# PCB_Draft_0.net
KiCad netlist of a schematic drawn in EAGLE
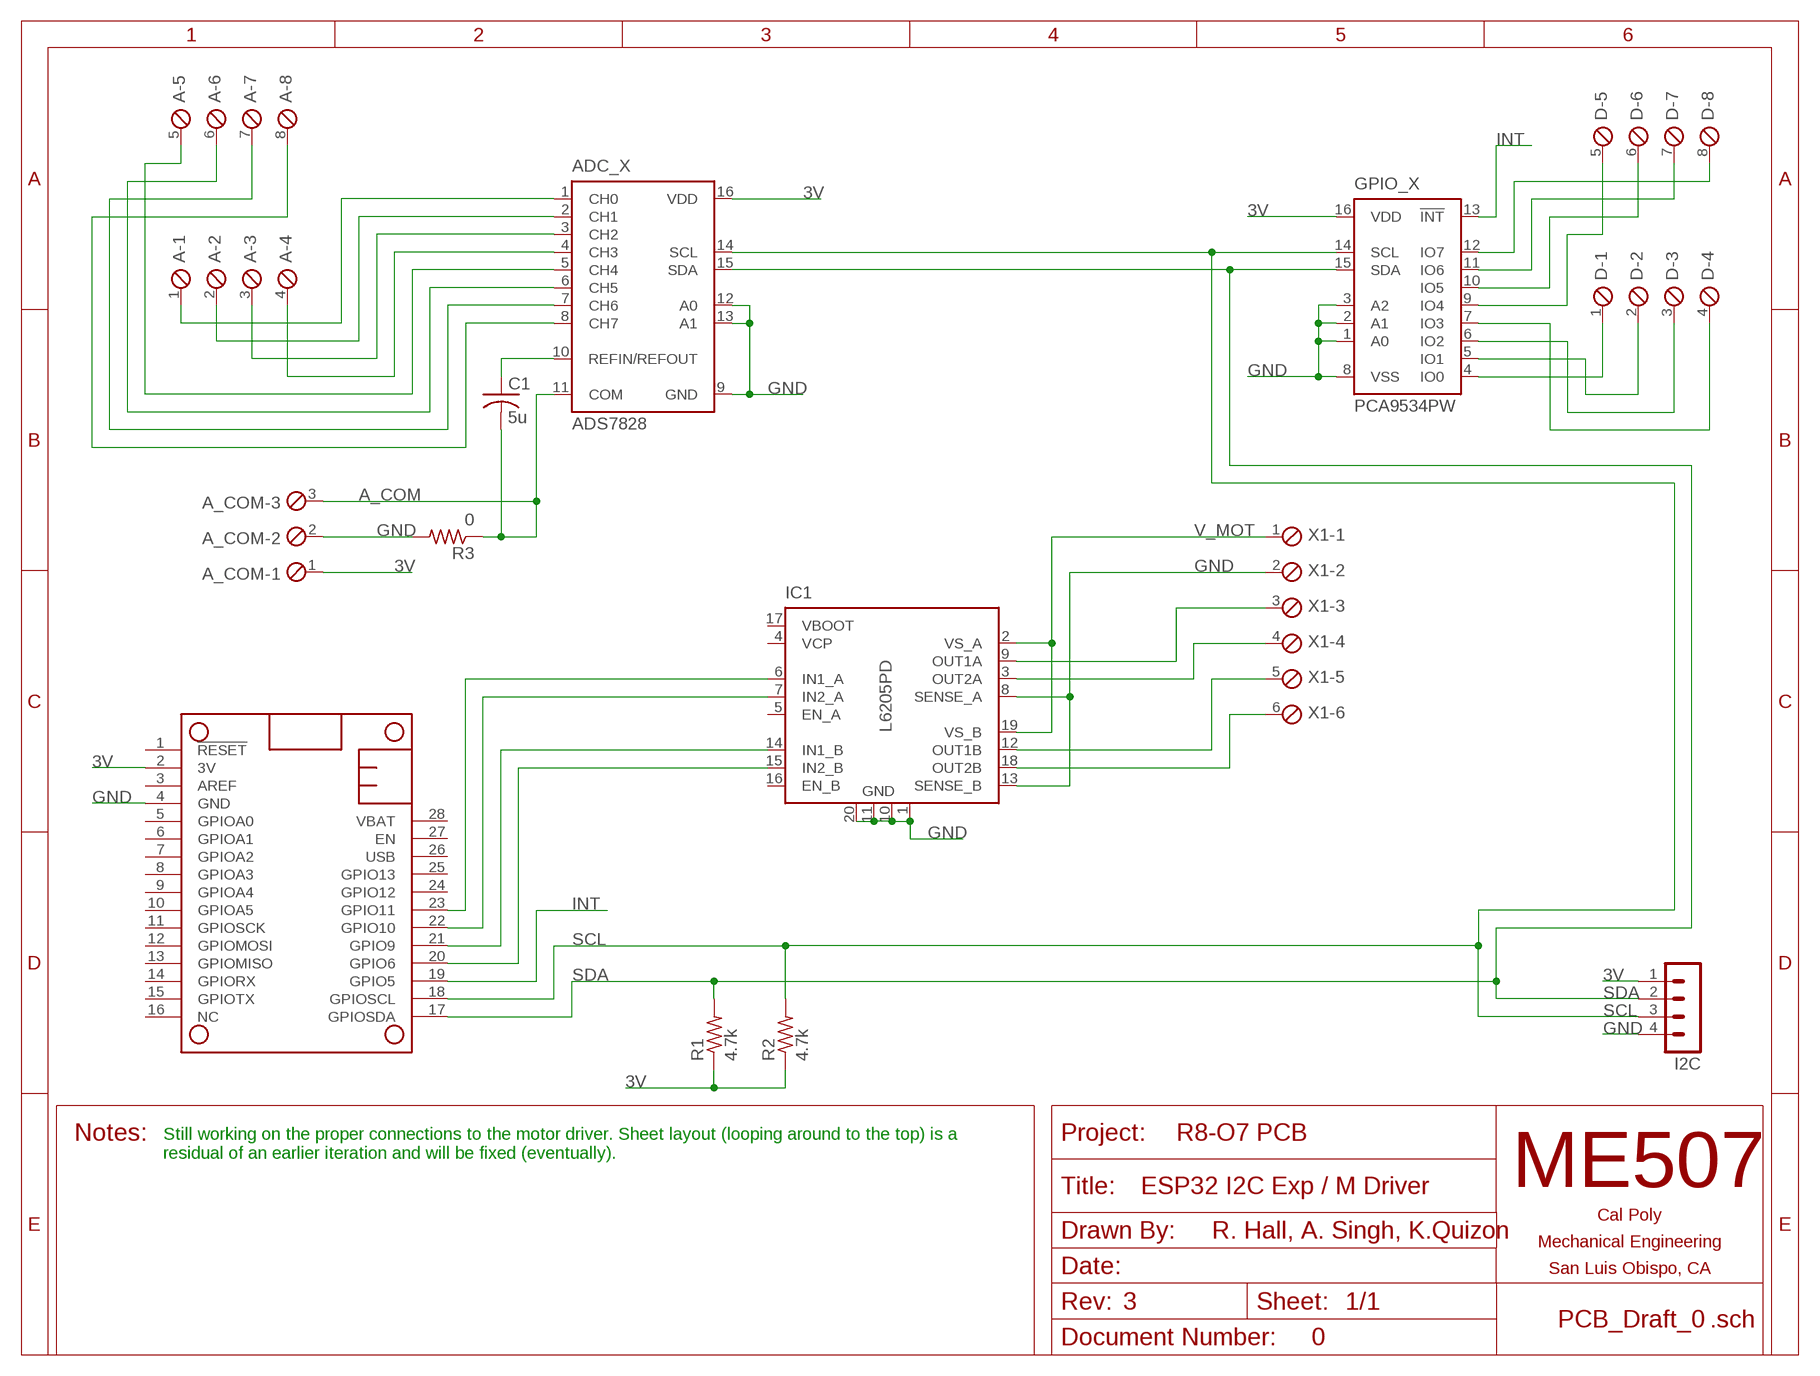
[diagram p0: schematic, sheet 1]

(export (version "E")
  (design (tool "Eeschema 10.0.6"))
  (components
    (comp (ref "A")
      (value "SCREWTERM_8P_254")
      (footprint "eagle-import:8POL254")
      (libsource (lib "eagle-import") (part "SCREWTERM_8P_254"))
    )
    (comp (ref "ADC_X")
      (value "ADS7828")
      (footprint "eagle-import:TSSOP16-PW")
      (fields (field (name "MF") "TEXAS INSTRUMENTS") (field (name "MPN") "ADS7828E/250"))
      (libsource (lib "eagle-import") (part "ADS7828"))
    )
    (comp (ref "A_COM")
      (value "SCREWTERM_3P_254")
      (footprint "eagle-import:3POL254")
      (libsource (lib "eagle-import") (part "SCREWTERM_3P_254"))
    )
    (comp (ref "C1")
      (value "5u")
      (footprint "eagle-import:C0805")
      (libsource (lib "eagle-import") (part "C-USC0805"))
    )
    (comp (ref "D")
      (value "SCREWTERM_8P_254")
      (footprint "eagle-import:8POL254")
      (libsource (lib "eagle-import") (part "SCREWTERM_8P_254"))
    )
    (comp (ref "GPIO_X")
      (value "PCA9534PW")
      (footprint "eagle-import:TSSOP16")
      (libsource (lib "eagle-import") (part "PCA9534PW"))
    )
    (comp (ref "I2C")
      (value "MA04-1")
      (footprint "eagle-import:MA04-1")
      (libsource (lib "eagle-import") (part "MA04-1"))
    )
    (comp (ref "IC1")
      (value "L6205PD")
      (footprint "eagle-import:POWERSO-20")
      (fields (field (name "MF") "Arrow Electronics"))
      (libsource (lib "eagle-import") (part "L6205PD"))
    )
    (comp (ref "MS1")
      (value "FEATHERWINGEXTENDED_BOTH_ENDS")
      (footprint "eagle-import:FEATHERWING")
      (libsource (lib "eagle-import") (part "FEATHERWINGEXTENDED_BOTH_ENDS"))
    )
    (comp (ref "R1")
      (value "4.7k")
      (footprint "eagle-import:R0805")
      (libsource (lib "eagle-import") (part "R-US_R0805"))
    )
    (comp (ref "R2")
      (value "4.7k")
      (footprint "eagle-import:R0805")
      (libsource (lib "eagle-import") (part "R-US_R0805"))
    )
    (comp (ref "R3")
      (value "0")
      (footprint "eagle-import:M0805")
      (libsource (lib "eagle-import") (part "R-US_M0805"))
    )
    (comp (ref "X1")
      (value "SCREWTERM_6P_254")
      (footprint "eagle-import:6POL254")
      (libsource (lib "eagle-import") (part "SCREWTERM_6P_254"))
    )
  )
  (nets
    (net (code "1") (name "/3V") (class "Default")
      (node (ref "ADC_X") (pin "16") (pinfunction "VDD_16") (pintype "power_in"))
      (node (ref "A_COM") (pin "1") (pinfunction "1_1") (pintype "passive"))
      (node (ref "GPIO_X") (pin "16") (pinfunction "VDD_16") (pintype "power_in"))
      (node (ref "I2C") (pin "1") (pinfunction "1_1") (pintype "passive"))
      (node (ref "MS1") (pin "2") (pinfunction "3V_2") (pintype "power_in"))
      (node (ref "R1") (pin "1") (pinfunction "1_1") (pintype "passive"))
      (node (ref "R2") (pin "1") (pinfunction "1_1") (pintype "passive"))
    )
    (net (code "2") (name "/A_COM") (class "Default")
      (node (ref "ADC_X") (pin "11") (pinfunction "COM_11") (pintype "input"))
      (node (ref "A_COM") (pin "3") (pinfunction "1_3") (pintype "passive"))
      (node (ref "C1") (pin "2") (pinfunction "2_2") (pintype "passive"))
      (node (ref "R3") (pin "1") (pinfunction "1_1") (pintype "passive"))
    )
    (net (code "3") (name "/GND") (class "Default")
      (node (ref "ADC_X") (pin "12") (pinfunction "A0_12") (pintype "input"))
      (node (ref "ADC_X") (pin "13") (pinfunction "A1_13") (pintype "input"))
      (node (ref "ADC_X") (pin "9") (pinfunction "GND_9") (pintype "power_in"))
      (node (ref "A_COM") (pin "2") (pinfunction "1_2") (pintype "passive"))
      (node (ref "GPIO_X") (pin "1") (pinfunction "A0_1") (pintype "input"))
      (node (ref "GPIO_X") (pin "2") (pinfunction "A1_2") (pintype "input"))
      (node (ref "GPIO_X") (pin "3") (pinfunction "A2_3") (pintype "input"))
      (node (ref "GPIO_X") (pin "8") (pinfunction "VSS_8") (pintype "power_in"))
      (node (ref "I2C") (pin "4") (pinfunction "4_4") (pintype "passive"))
      (node (ref "IC1") (pin "1") (pinfunction "GND_1") (pintype "power_in"))
      (node (ref "IC1") (pin "10") (pinfunction "GND_10") (pintype "power_in"))
      (node (ref "IC1") (pin "11") (pinfunction "GND_11") (pintype "power_in"))
      (node (ref "IC1") (pin "13") (pinfunction "SENSE_B_13") (pintype "input"))
      (node (ref "IC1") (pin "20") (pinfunction "GND_20") (pintype "power_in"))
      (node (ref "IC1") (pin "8") (pinfunction "SENSE_A_8") (pintype "input"))
      (node (ref "MS1") (pin "4") (pinfunction "GND_4") (pintype "power_in"))
      (node (ref "R3") (pin "2") (pinfunction "2_2") (pintype "passive"))
      (node (ref "X1") (pin "2") (pinfunction "1_2") (pintype "passive"))
    )
    (net (code "4") (name "/INT") (class "Default")
      (node (ref "GPIO_X") (pin "13") (pinfunction "~{INT}_13") (pintype "open_collector"))
      (node (ref "MS1") (pin "19") (pinfunction "GPIO5_19") (pintype "bidirectional"))
    )
    (net (code "5") (name "/SCL") (class "Default")
      (node (ref "ADC_X") (pin "14") (pinfunction "SCL_14") (pintype "input"))
      (node (ref "GPIO_X") (pin "14") (pinfunction "SCL_14") (pintype "input"))
      (node (ref "I2C") (pin "3") (pinfunction "3_3") (pintype "passive"))
      (node (ref "MS1") (pin "18") (pinfunction "GPIOSCL_18") (pintype "bidirectional"))
      (node (ref "R2") (pin "2") (pinfunction "2_2") (pintype "passive"))
    )
    (net (code "6") (name "/SDA") (class "Default")
      (node (ref "ADC_X") (pin "15") (pinfunction "SDA_15") (pintype "bidirectional"))
      (node (ref "GPIO_X") (pin "15") (pinfunction "SDA_15") (pintype "bidirectional"))
      (node (ref "I2C") (pin "2") (pinfunction "2_2") (pintype "passive"))
      (node (ref "MS1") (pin "17") (pinfunction "GPIOSDA_17") (pintype "bidirectional"))
      (node (ref "R1") (pin "2") (pinfunction "2_2") (pintype "passive"))
    )
    (net (code "7") (name "/USB") (class "Default")
      (node (ref "MS1") (pin "26") (pinfunction "USB_26") (pintype "power_in"))
    )
    (net (code "8") (name "/VBAT") (class "Default")
      (node (ref "MS1") (pin "28") (pinfunction "VBAT_28") (pintype "power_in"))
    )
    (net (code "9") (name "/VBOOT") (class "Default")
      (node (ref "IC1") (pin "17") (pinfunction "VBOOT_17") (pintype "power_in"))
    )
    (net (code "10") (name "/VCP") (class "Default")
      (node (ref "IC1") (pin "4") (pinfunction "VCP_4") (pintype "power_in"))
    )
    (net (code "11") (name "/V_MOT") (class "Default")
      (node (ref "IC1") (pin "19") (pinfunction "VS_B_19") (pintype "power_in"))
      (node (ref "IC1") (pin "2") (pinfunction "VS_A_2") (pintype "power_in"))
      (node (ref "X1") (pin "1") (pinfunction "1_1") (pintype "passive"))
    )
    (net (code "12") (name "Net-(AB-1)") (class "Default")
      (node (ref "A") (pin "2") (pinfunction "1_2") (pintype "passive"))
      (node (ref "ADC_X") (pin "2") (pinfunction "CH1_2") (pintype "input"))
    )
    (net (code "13") (name "Net-(AC-1)") (class "Default")
      (node (ref "A") (pin "3") (pinfunction "1_3") (pintype "passive"))
      (node (ref "ADC_X") (pin "3") (pinfunction "CH2_3") (pintype "input"))
    )
    (net (code "14") (name "Net-(AD-1)") (class "Default")
      (node (ref "A") (pin "4") (pinfunction "1_4") (pintype "passive"))
      (node (ref "ADC_X") (pin "4") (pinfunction "CH3_4") (pintype "input"))
    )
    (net (code "15") (name "Net-(ADC_X-CH0)") (class "Default")
      (node (ref "A") (pin "1") (pinfunction "1_1") (pintype "passive"))
      (node (ref "ADC_X") (pin "1") (pinfunction "CH0_1") (pintype "input"))
    )
    (net (code "16") (name "Net-(ADC_X-CH4)") (class "Default")
      (node (ref "A") (pin "5") (pinfunction "1_5") (pintype "passive"))
      (node (ref "ADC_X") (pin "5") (pinfunction "CH4_5") (pintype "input"))
    )
    (net (code "17") (name "Net-(ADC_X-CH5)") (class "Default")
      (node (ref "A") (pin "6") (pinfunction "1_6") (pintype "passive"))
      (node (ref "ADC_X") (pin "6") (pinfunction "CH5_6") (pintype "input"))
    )
    (net (code "18") (name "Net-(ADC_X-CH6)") (class "Default")
      (node (ref "A") (pin "7") (pinfunction "1_7") (pintype "passive"))
      (node (ref "ADC_X") (pin "7") (pinfunction "CH6_7") (pintype "input"))
    )
    (net (code "19") (name "Net-(ADC_X-CH7)") (class "Default")
      (node (ref "A") (pin "8") (pinfunction "1_8") (pintype "passive"))
      (node (ref "ADC_X") (pin "8") (pinfunction "CH7_8") (pintype "input"))
    )
    (net (code "20") (name "Net-(ADC_X-REFIN{slash}REFOUT)") (class "Default")
      (node (ref "ADC_X") (pin "10") (pinfunction "REFIN/REFOUT_10") (pintype "passive"))
      (node (ref "C1") (pin "1") (pinfunction "1_1") (pintype "passive"))
    )
    (net (code "21") (name "Net-(DB-1)") (class "Default")
      (node (ref "D") (pin "2") (pinfunction "1_2") (pintype "passive"))
      (node (ref "GPIO_X") (pin "5") (pinfunction "IO1_5") (pintype "bidirectional"))
    )
    (net (code "22") (name "Net-(DC-1)") (class "Default")
      (node (ref "D") (pin "3") (pinfunction "1_3") (pintype "passive"))
      (node (ref "GPIO_X") (pin "6") (pinfunction "IO2_6") (pintype "bidirectional"))
    )
    (net (code "23") (name "Net-(DD-1)") (class "Default")
      (node (ref "D") (pin "4") (pinfunction "1_4") (pintype "passive"))
      (node (ref "GPIO_X") (pin "7") (pinfunction "IO3_7") (pintype "bidirectional"))
    )
    (net (code "24") (name "Net-(DE-1)") (class "Default")
      (node (ref "D") (pin "5") (pinfunction "1_5") (pintype "passive"))
      (node (ref "GPIO_X") (pin "9") (pinfunction "IO4_9") (pintype "bidirectional"))
    )
    (net (code "25") (name "Net-(DF-1)") (class "Default")
      (node (ref "D") (pin "6") (pinfunction "1_6") (pintype "passive"))
      (node (ref "GPIO_X") (pin "10") (pinfunction "IO5_10") (pintype "bidirectional"))
    )
    (net (code "26") (name "Net-(DG-1)") (class "Default")
      (node (ref "D") (pin "7") (pinfunction "1_7") (pintype "passive"))
      (node (ref "GPIO_X") (pin "11") (pinfunction "IO6_11") (pintype "bidirectional"))
    )
    (net (code "27") (name "Net-(DH-1)") (class "Default")
      (node (ref "D") (pin "8") (pinfunction "1_8") (pintype "passive"))
      (node (ref "GPIO_X") (pin "12") (pinfunction "IO7_12") (pintype "bidirectional"))
    )
    (net (code "28") (name "Net-(GPIO_X-IO0)") (class "Default")
      (node (ref "D") (pin "1") (pinfunction "1_1") (pintype "passive"))
      (node (ref "GPIO_X") (pin "4") (pinfunction "IO0_4") (pintype "bidirectional"))
    )
    (net (code "29") (name "Net-(IC1-IN1_A)") (class "Default")
      (node (ref "IC1") (pin "6") (pinfunction "IN1_A_6") (pintype "input"))
      (node (ref "MS1") (pin "23") (pinfunction "GPIO11_23") (pintype "bidirectional"))
    )
    (net (code "30") (name "Net-(IC1-IN1_B)") (class "Default")
      (node (ref "IC1") (pin "14") (pinfunction "IN1_B_14") (pintype "input"))
      (node (ref "MS1") (pin "21") (pinfunction "GPIO9_21") (pintype "bidirectional"))
    )
    (net (code "31") (name "Net-(IC1-IN2_A)") (class "Default")
      (node (ref "IC1") (pin "7") (pinfunction "IN2_A_7") (pintype "input"))
      (node (ref "MS1") (pin "22") (pinfunction "GPIO10_22") (pintype "bidirectional"))
    )
    (net (code "32") (name "Net-(IC1-IN2_B)") (class "Default")
      (node (ref "IC1") (pin "15") (pinfunction "IN2_B_15") (pintype "input"))
      (node (ref "MS1") (pin "20") (pinfunction "GPIO6_20") (pintype "bidirectional"))
    )
    (net (code "33") (name "Net-(IC1-OUT1A)") (class "Default")
      (node (ref "IC1") (pin "9") (pinfunction "OUT1A_9") (pintype "output"))
      (node (ref "X1") (pin "3") (pinfunction "1_3") (pintype "passive"))
    )
    (net (code "34") (name "Net-(IC1-OUT1B)") (class "Default")
      (node (ref "IC1") (pin "12") (pinfunction "OUT1B_12") (pintype "output"))
      (node (ref "X1") (pin "5") (pinfunction "1_5") (pintype "passive"))
    )
    (net (code "35") (name "Net-(IC1-OUT2A)") (class "Default")
      (node (ref "IC1") (pin "3") (pinfunction "OUT2A_3") (pintype "output"))
      (node (ref "X1") (pin "4") (pinfunction "1_4") (pintype "passive"))
    )
    (net (code "36") (name "Net-(IC1-OUT2B)") (class "Default")
      (node (ref "IC1") (pin "18") (pinfunction "OUT2B_18") (pintype "output"))
      (node (ref "X1") (pin "6") (pinfunction "1_6") (pintype "passive"))
    )
    (net (code "37") (name "unconnected-(IC1-EN_A-Pad5)") (class "Default")
      (node (ref "IC1") (pin "5") (pinfunction "EN_A_5") (pintype "input"))
    )
    (net (code "38") (name "unconnected-(IC1-EN_B-Pad16)") (class "Default")
      (node (ref "IC1") (pin "16") (pinfunction "EN_B_16") (pintype "input"))
    )
    (net (code "39") (name "unconnected-(MS1-AREF-Pad3)") (class "Default")
      (node (ref "MS1") (pin "3") (pinfunction "AREF_3") (pintype "passive"))
    )
    (net (code "40") (name "unconnected-(MS1-EN-Pad27)") (class "Default")
      (node (ref "MS1") (pin "27") (pinfunction "EN_27") (pintype "passive"))
    )
    (net (code "41") (name "unconnected-(MS1-GPIO12-Pad24)") (class "Default")
      (node (ref "MS1") (pin "24") (pinfunction "GPIO12_24") (pintype "bidirectional"))
    )
    (net (code "42") (name "unconnected-(MS1-GPIO13-Pad25)") (class "Default")
      (node (ref "MS1") (pin "25") (pinfunction "GPIO13_25") (pintype "bidirectional"))
    )
    (net (code "43") (name "unconnected-(MS1-GPIOA0-Pad5)") (class "Default")
      (node (ref "MS1") (pin "5") (pinfunction "GPIOA0_5") (pintype "bidirectional"))
    )
    (net (code "44") (name "unconnected-(MS1-GPIOA1-Pad6)") (class "Default")
      (node (ref "MS1") (pin "6") (pinfunction "GPIOA1_6") (pintype "bidirectional"))
    )
    (net (code "45") (name "unconnected-(MS1-GPIOA2-Pad7)") (class "Default")
      (node (ref "MS1") (pin "7") (pinfunction "GPIOA2_7") (pintype "bidirectional"))
    )
    (net (code "46") (name "unconnected-(MS1-GPIOA3-Pad8)") (class "Default")
      (node (ref "MS1") (pin "8") (pinfunction "GPIOA3_8") (pintype "bidirectional"))
    )
    (net (code "47") (name "unconnected-(MS1-GPIOA4-Pad9)") (class "Default")
      (node (ref "MS1") (pin "9") (pinfunction "GPIOA4_9") (pintype "bidirectional"))
    )
    (net (code "48") (name "unconnected-(MS1-GPIOA5-Pad10)") (class "Default")
      (node (ref "MS1") (pin "10") (pinfunction "GPIOA5_10") (pintype "bidirectional"))
    )
    (net (code "49") (name "unconnected-(MS1-GPIOMISO-Pad13)") (class "Default")
      (node (ref "MS1") (pin "13") (pinfunction "GPIOMISO_13") (pintype "bidirectional"))
    )
    (net (code "50") (name "unconnected-(MS1-GPIOMOSI-Pad12)") (class "Default")
      (node (ref "MS1") (pin "12") (pinfunction "GPIOMOSI_12") (pintype "bidirectional"))
    )
    (net (code "51") (name "unconnected-(MS1-GPIORX-Pad14)") (class "Default")
      (node (ref "MS1") (pin "14") (pinfunction "GPIORX_14") (pintype "bidirectional"))
    )
    (net (code "52") (name "unconnected-(MS1-GPIOSCK-Pad11)") (class "Default")
      (node (ref "MS1") (pin "11") (pinfunction "GPIOSCK_11") (pintype "bidirectional"))
    )
    (net (code "53") (name "unconnected-(MS1-GPIOTX-Pad15)") (class "Default")
      (node (ref "MS1") (pin "15") (pinfunction "GPIOTX_15") (pintype "bidirectional"))
    )
    (net (code "54") (name "unconnected-(MS1-NC-Pad16)") (class "Default")
      (node (ref "MS1") (pin "16") (pinfunction "NC_16") (pintype "passive"))
    )
    (net (code "55") (name "unconnected-(MS1-~{RESET}-Pad1)") (class "Default")
      (node (ref "MS1") (pin "1") (pinfunction "~{RESET}_1") (pintype "input"))
    )
  )
)
